# MotorEncoder.net
KiCad netlist of a schematic drawn in EAGLE
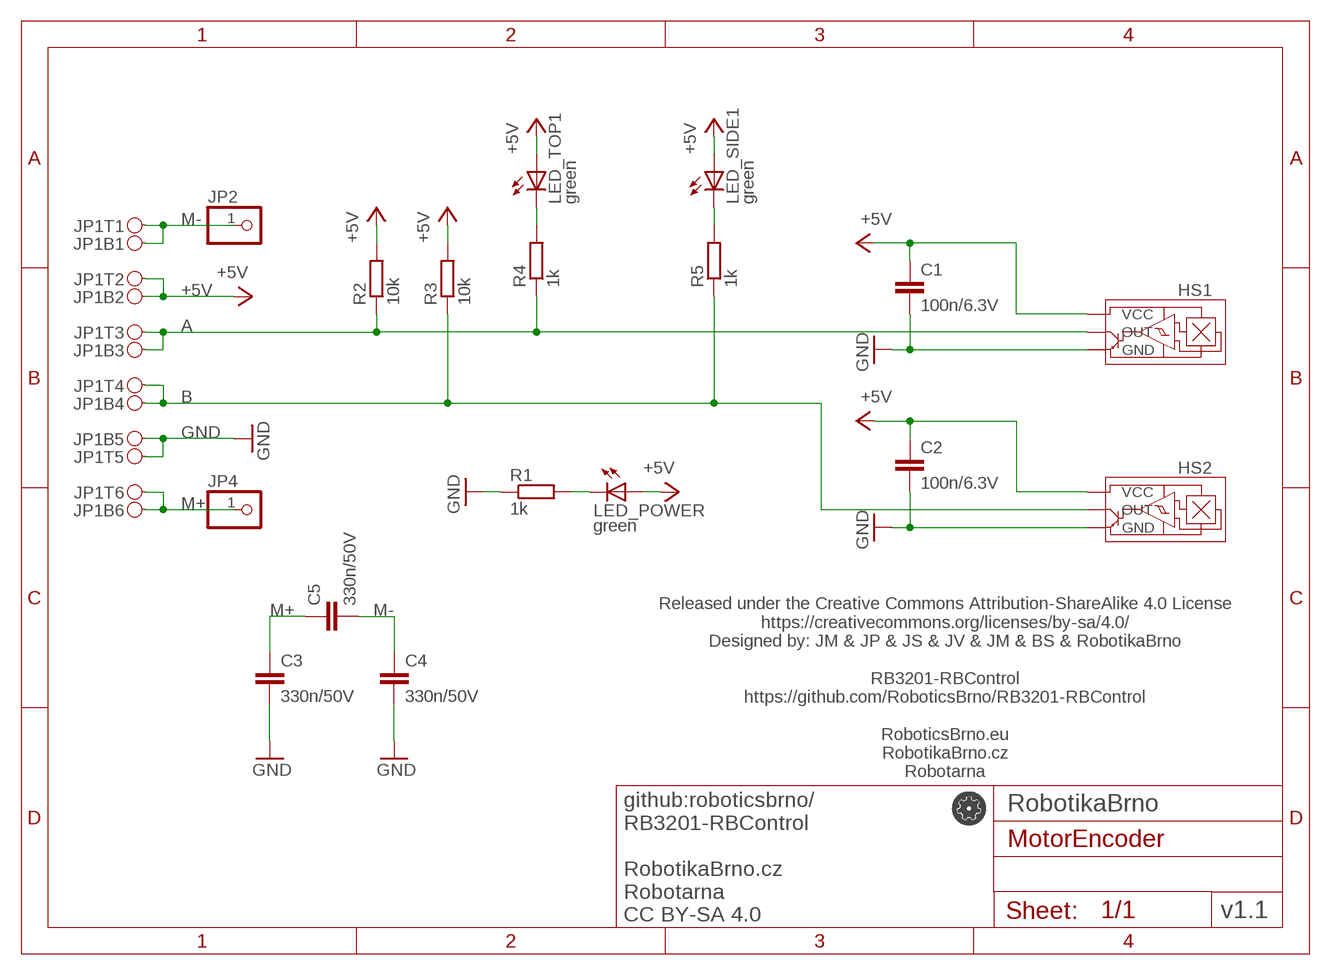
[diagram p0: schematic, sheet 1]

(export (version "E")
  (design (tool "Eeschema 10.0.6"))
  (components
    (comp (ref "C1")
      (value "100n/6.3V")
      (footprint "eagle-import:C0402")
      (libsource (lib "eagle-import") (part "C-EUC0402"))
    )
    (comp (ref "C2")
      (value "100n/6.3V")
      (footprint "eagle-import:C0402")
      (libsource (lib "eagle-import") (part "C-EUC0402"))
    )
    (comp (ref "C3")
      (value "330n/50V")
      (footprint "eagle-import:C0805")
      (libsource (lib "eagle-import") (part "C-EUC0805"))
    )
    (comp (ref "C4")
      (value "330n/50V")
      (footprint "eagle-import:C0805")
      (libsource (lib "eagle-import") (part "C-EUC0805"))
    )
    (comp (ref "C5")
      (value "330n/50V")
      (footprint "eagle-import:C0805")
      (libsource (lib "eagle-import") (part "C-EUC0805"))
    )
    (comp (ref "HS1")
      (value "HALL")
      (footprint "eagle-import:SMD_TH")
      (libsource (lib "eagle-import") (part "HALL"))
    )
    (comp (ref "HS2")
      (value "HALL")
      (footprint "eagle-import:SMD_TH")
      (libsource (lib "eagle-import") (part "HALL"))
    )
    (comp (ref "JP1")
      (value "PINH2X06")
      (footprint "eagle-import:PINH2X06SMD")
      (libsource (lib "eagle-import") (part "PINH2X06"))
    )
    (comp (ref "JP2")
      (value "PINHD-1X1")
      (footprint "eagle-import:1X01")
      (libsource (lib "eagle-import") (part "PINHD-1X1"))
    )
    (comp (ref "JP4")
      (value "PINHD-1X1")
      (footprint "eagle-import:1X01")
      (libsource (lib "eagle-import") (part "PINHD-1X1"))
    )
    (comp (ref "LED_POWER")
      (value "green")
      (footprint "eagle-import:CHIPLED_0603")
      (libsource (lib "eagle-import") (part "LEDCHIPLED_0603"))
    )
    (comp (ref "LED_SIDE1")
      (value "green")
      (footprint "eagle-import:CHIPLED_0603")
      (libsource (lib "eagle-import") (part "LEDCHIPLED_0603"))
    )
    (comp (ref "LED_TOP1")
      (value "green")
      (footprint "eagle-import:CHIPLED_0603")
      (libsource (lib "eagle-import") (part "LEDCHIPLED_0603"))
    )
    (comp (ref "R1")
      (value "1k")
      (footprint "eagle-import:R0603")
      (libsource (lib "eagle-import") (part "R-EU_R0603"))
    )
    (comp (ref "R2")
      (value "10k")
      (footprint "eagle-import:R0603")
      (libsource (lib "eagle-import") (part "R-EU_R0603"))
    )
    (comp (ref "R3")
      (value "10k")
      (footprint "eagle-import:R0603")
      (libsource (lib "eagle-import") (part "R-EU_R0603"))
    )
    (comp (ref "R4")
      (value "1k")
      (footprint "eagle-import:R0603")
      (libsource (lib "eagle-import") (part "R-EU_R0603"))
    )
    (comp (ref "R5")
      (value "1k")
      (footprint "eagle-import:R0603")
      (libsource (lib "eagle-import") (part "R-EU_R0603"))
    )
  )
  (nets
    (net (code "1") (name "+5V") (class "Default")
      (node (ref "C1") (pin "1") (pinfunction "1_1") (pintype "passive"))
      (node (ref "C2") (pin "1") (pinfunction "1_1") (pintype "passive"))
      (node (ref "HS1") (pin "VCC") (pinfunction "VCC_VCC") (pintype "power_in"))
      (node (ref "HS2") (pin "VCC") (pinfunction "VCC_VCC") (pintype "power_in"))
      (node (ref "JP1") (pin "B2") (pinfunction "1_B2") (pintype "passive"))
      (node (ref "JP1") (pin "T2") (pinfunction "1_T2") (pintype "passive"))
      (node (ref "LED_POWER") (pin "A") (pinfunction "A_A") (pintype "passive"))
      (node (ref "LED_SIDE1") (pin "A") (pinfunction "A_A") (pintype "passive"))
      (node (ref "LED_TOP1") (pin "A") (pinfunction "A_A") (pintype "passive"))
      (node (ref "R2") (pin "2") (pinfunction "2_2") (pintype "passive"))
      (node (ref "R3") (pin "2") (pinfunction "2_2") (pintype "passive"))
    )
    (net (code "2") (name "/A") (class "Default")
      (node (ref "HS1") (pin "OUT") (pinfunction "OUT_OUT") (pintype "open_collector"))
      (node (ref "JP1") (pin "B3") (pinfunction "1_B3") (pintype "passive"))
      (node (ref "JP1") (pin "T3") (pinfunction "1_T3") (pintype "passive"))
      (node (ref "R2") (pin "1") (pinfunction "1_1") (pintype "passive"))
      (node (ref "R4") (pin "1") (pinfunction "1_1") (pintype "passive"))
    )
    (net (code "3") (name "/B") (class "Default")
      (node (ref "HS2") (pin "OUT") (pinfunction "OUT_OUT") (pintype "open_collector"))
      (node (ref "JP1") (pin "B4") (pinfunction "1_B4") (pintype "passive"))
      (node (ref "JP1") (pin "T4") (pinfunction "1_T4") (pintype "passive"))
      (node (ref "R3") (pin "1") (pinfunction "1_1") (pintype "passive"))
      (node (ref "R5") (pin "1") (pinfunction "1_1") (pintype "passive"))
    )
    (net (code "4") (name "/M+") (class "Default")
      (node (ref "C3") (pin "1") (pinfunction "1_1") (pintype "passive"))
      (node (ref "C5") (pin "1") (pinfunction "1_1") (pintype "passive"))
      (node (ref "JP1") (pin "B6") (pinfunction "1_B6") (pintype "passive"))
      (node (ref "JP1") (pin "T6") (pinfunction "1_T6") (pintype "passive"))
      (node (ref "JP4") (pin "1") (pinfunction "1_1") (pintype "passive"))
    )
    (net (code "5") (name "/M-") (class "Default")
      (node (ref "C4") (pin "1") (pinfunction "1_1") (pintype "passive"))
      (node (ref "C5") (pin "2") (pinfunction "2_2") (pintype "passive"))
      (node (ref "JP1") (pin "B1") (pinfunction "1_B1") (pintype "passive"))
      (node (ref "JP1") (pin "T1") (pinfunction "1_T1") (pintype "passive"))
      (node (ref "JP2") (pin "1") (pinfunction "1_1") (pintype "passive"))
    )
    (net (code "6") (name "GND") (class "Default")
      (node (ref "C1") (pin "2") (pinfunction "2_2") (pintype "passive"))
      (node (ref "C2") (pin "2") (pinfunction "2_2") (pintype "passive"))
      (node (ref "C3") (pin "2") (pinfunction "2_2") (pintype "passive"))
      (node (ref "C4") (pin "2") (pinfunction "2_2") (pintype "passive"))
      (node (ref "HS1") (pin "GND") (pinfunction "GND_GND") (pintype "power_in"))
      (node (ref "HS2") (pin "GND") (pinfunction "GND_GND") (pintype "power_in"))
      (node (ref "JP1") (pin "B5") (pinfunction "1_B5") (pintype "passive"))
      (node (ref "JP1") (pin "T5") (pinfunction "1_T5") (pintype "passive"))
      (node (ref "R1") (pin "1") (pinfunction "1_1") (pintype "passive"))
    )
    (net (code "7") (name "Net-(LED_POWER-PadC)") (class "Default")
      (node (ref "LED_POWER") (pin "C") (pinfunction "C_C") (pintype "passive"))
      (node (ref "R1") (pin "2") (pinfunction "2_2") (pintype "passive"))
    )
    (net (code "8") (name "Net-(LED_SIDE1-PadC)") (class "Default")
      (node (ref "LED_SIDE1") (pin "C") (pinfunction "C_C") (pintype "passive"))
      (node (ref "R5") (pin "2") (pinfunction "2_2") (pintype "passive"))
    )
    (net (code "9") (name "Net-(LED_TOP1-PadC)") (class "Default")
      (node (ref "LED_TOP1") (pin "C") (pinfunction "C_C") (pintype "passive"))
      (node (ref "R4") (pin "2") (pinfunction "2_2") (pintype "passive"))
    )
  )
)
